# WS2812_MATRIX_2.net
KiCad netlist of a schematic drawn in Altium Designer
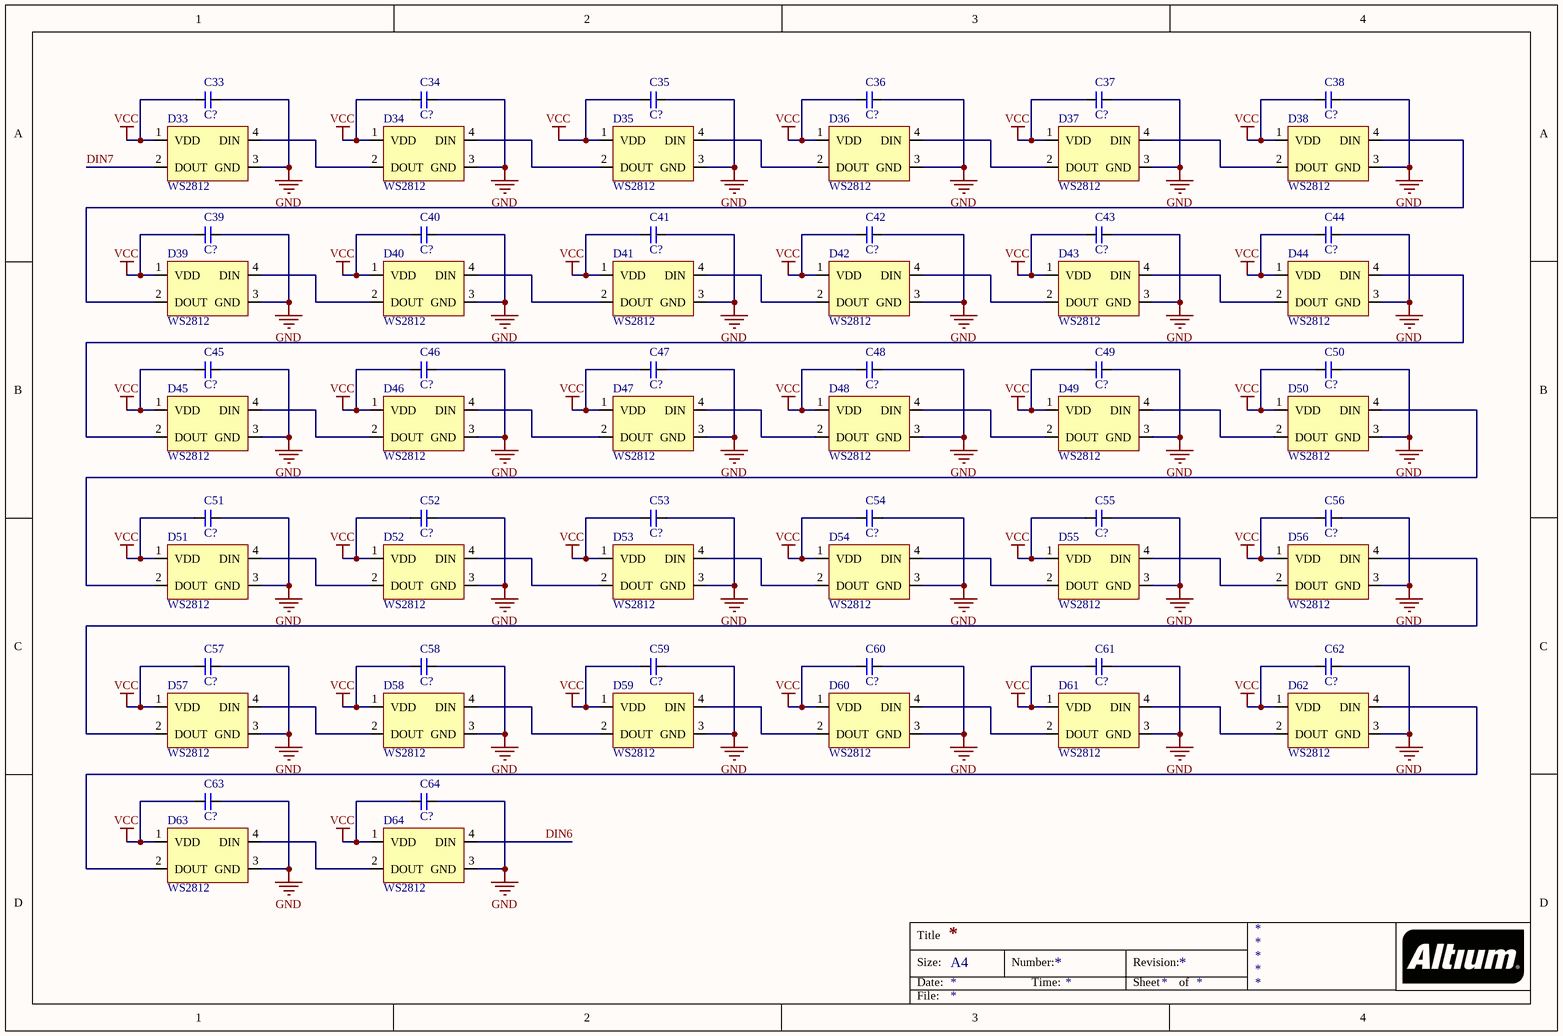
[diagram p0: WS2812_MATRIX_2.SchDoc]

(export (version "E")
  (design (tool "Eeschema 10.0.6"))
  (components
    (comp (ref "C33")
      (value "C?")
      (footprint "C0603")
      (description "Cap")
      (libsource (lib "SCH_Bacsic") (part "CAP"))
    )
    (comp (ref "C34")
      (value "C?")
      (footprint "C0603")
      (description "Cap")
      (libsource (lib "SCH_Bacsic") (part "CAP"))
    )
    (comp (ref "C35")
      (value "C?")
      (footprint "C0603")
      (description "Cap")
      (libsource (lib "SCH_Bacsic") (part "CAP"))
    )
    (comp (ref "C36")
      (value "C?")
      (footprint "C0603")
      (description "Cap")
      (libsource (lib "SCH_Bacsic") (part "CAP"))
    )
    (comp (ref "C37")
      (value "C?")
      (footprint "C0603")
      (description "Cap")
      (libsource (lib "SCH_Bacsic") (part "CAP"))
    )
    (comp (ref "C38")
      (value "C?")
      (footprint "C0603")
      (description "Cap")
      (libsource (lib "SCH_Bacsic") (part "CAP"))
    )
    (comp (ref "C39")
      (value "C?")
      (footprint "C0603")
      (description "Cap")
      (libsource (lib "SCH_Bacsic") (part "CAP"))
    )
    (comp (ref "C40")
      (value "C?")
      (footprint "C0603")
      (description "Cap")
      (libsource (lib "SCH_Bacsic") (part "CAP"))
    )
    (comp (ref "C41")
      (value "C?")
      (footprint "C0603")
      (description "Cap")
      (libsource (lib "SCH_Bacsic") (part "CAP"))
    )
    (comp (ref "C42")
      (value "C?")
      (footprint "C0603")
      (description "Cap")
      (libsource (lib "SCH_Bacsic") (part "CAP"))
    )
    (comp (ref "C43")
      (value "C?")
      (footprint "C0603")
      (description "Cap")
      (libsource (lib "SCH_Bacsic") (part "CAP"))
    )
    (comp (ref "C44")
      (value "C?")
      (footprint "C0603")
      (description "Cap")
      (libsource (lib "SCH_Bacsic") (part "CAP"))
    )
    (comp (ref "C45")
      (value "C?")
      (footprint "C0603")
      (description "Cap")
      (libsource (lib "SCH_Bacsic") (part "CAP"))
    )
    (comp (ref "C46")
      (value "C?")
      (footprint "C0603")
      (description "Cap")
      (libsource (lib "SCH_Bacsic") (part "CAP"))
    )
    (comp (ref "C47")
      (value "C?")
      (footprint "C0603")
      (description "Cap")
      (libsource (lib "SCH_Bacsic") (part "CAP"))
    )
    (comp (ref "C48")
      (value "C?")
      (footprint "C0603")
      (description "Cap")
      (libsource (lib "SCH_Bacsic") (part "CAP"))
    )
    (comp (ref "C49")
      (value "C?")
      (footprint "C0603")
      (description "Cap")
      (libsource (lib "SCH_Bacsic") (part "CAP"))
    )
    (comp (ref "C50")
      (value "C?")
      (footprint "C0603")
      (description "Cap")
      (libsource (lib "SCH_Bacsic") (part "CAP"))
    )
    (comp (ref "C51")
      (value "C?")
      (footprint "C0603")
      (description "Cap")
      (libsource (lib "SCH_Bacsic") (part "CAP"))
    )
    (comp (ref "C52")
      (value "C?")
      (footprint "C0603")
      (description "Cap")
      (libsource (lib "SCH_Bacsic") (part "CAP"))
    )
    (comp (ref "C53")
      (value "C?")
      (footprint "C0603")
      (description "Cap")
      (libsource (lib "SCH_Bacsic") (part "CAP"))
    )
    (comp (ref "C54")
      (value "C?")
      (footprint "C0603")
      (description "Cap")
      (libsource (lib "SCH_Bacsic") (part "CAP"))
    )
    (comp (ref "C55")
      (value "C?")
      (footprint "C0603")
      (description "Cap")
      (libsource (lib "SCH_Bacsic") (part "CAP"))
    )
    (comp (ref "C56")
      (value "C?")
      (footprint "C0603")
      (description "Cap")
      (libsource (lib "SCH_Bacsic") (part "CAP"))
    )
    (comp (ref "C57")
      (value "C?")
      (footprint "C0603")
      (description "Cap")
      (libsource (lib "SCH_Bacsic") (part "CAP"))
    )
    (comp (ref "C58")
      (value "C?")
      (footprint "C0603")
      (description "Cap")
      (libsource (lib "SCH_Bacsic") (part "CAP"))
    )
    (comp (ref "C59")
      (value "C?")
      (footprint "C0603")
      (description "Cap")
      (libsource (lib "SCH_Bacsic") (part "CAP"))
    )
    (comp (ref "C60")
      (value "C?")
      (footprint "C0603")
      (description "Cap")
      (libsource (lib "SCH_Bacsic") (part "CAP"))
    )
    (comp (ref "C61")
      (value "C?")
      (footprint "C0603")
      (description "Cap")
      (libsource (lib "SCH_Bacsic") (part "CAP"))
    )
    (comp (ref "C62")
      (value "C?")
      (footprint "C0603")
      (description "Cap")
      (libsource (lib "SCH_Bacsic") (part "CAP"))
    )
    (comp (ref "C63")
      (value "C?")
      (footprint "C0603")
      (description "Cap")
      (libsource (lib "SCH_Bacsic") (part "CAP"))
    )
    (comp (ref "C64")
      (value "C?")
      (footprint "C0603")
      (description "Cap")
      (libsource (lib "SCH_Bacsic") (part "CAP"))
    )
    (comp (ref "D33")
      (value "WS2812")
      (footprint "WS2812_3528")
      (libsource (lib "SCH_Bacsic") (part "WS2812"))
    )
    (comp (ref "D34")
      (value "WS2812")
      (footprint "WS2812_3528")
      (libsource (lib "SCH_Bacsic") (part "WS2812"))
    )
    (comp (ref "D35")
      (value "WS2812")
      (footprint "WS2812_3528")
      (libsource (lib "SCH_Bacsic") (part "WS2812"))
    )
    (comp (ref "D36")
      (value "WS2812")
      (footprint "WS2812_3528")
      (libsource (lib "SCH_Bacsic") (part "WS2812"))
    )
    (comp (ref "D37")
      (value "WS2812")
      (footprint "WS2812_3528")
      (libsource (lib "SCH_Bacsic") (part "WS2812"))
    )
    (comp (ref "D38")
      (value "WS2812")
      (footprint "WS2812_3528")
      (libsource (lib "SCH_Bacsic") (part "WS2812"))
    )
    (comp (ref "D39")
      (value "WS2812")
      (footprint "WS2812_3528")
      (libsource (lib "SCH_Bacsic") (part "WS2812"))
    )
    (comp (ref "D40")
      (value "WS2812")
      (footprint "WS2812_3528")
      (libsource (lib "SCH_Bacsic") (part "WS2812"))
    )
    (comp (ref "D41")
      (value "WS2812")
      (footprint "WS2812_3528")
      (libsource (lib "SCH_Bacsic") (part "WS2812"))
    )
    (comp (ref "D42")
      (value "WS2812")
      (footprint "WS2812_3528")
      (libsource (lib "SCH_Bacsic") (part "WS2812"))
    )
    (comp (ref "D43")
      (value "WS2812")
      (footprint "WS2812_3528")
      (libsource (lib "SCH_Bacsic") (part "WS2812"))
    )
    (comp (ref "D44")
      (value "WS2812")
      (footprint "WS2812_3528")
      (libsource (lib "SCH_Bacsic") (part "WS2812"))
    )
    (comp (ref "D45")
      (value "WS2812")
      (footprint "WS2812_3528")
      (libsource (lib "SCH_Bacsic") (part "WS2812"))
    )
    (comp (ref "D46")
      (value "WS2812")
      (footprint "WS2812_3528")
      (libsource (lib "SCH_Bacsic") (part "WS2812"))
    )
    (comp (ref "D47")
      (value "WS2812")
      (footprint "WS2812_3528")
      (libsource (lib "SCH_Bacsic") (part "WS2812"))
    )
    (comp (ref "D48")
      (value "WS2812")
      (footprint "WS2812_3528")
      (libsource (lib "SCH_Bacsic") (part "WS2812"))
    )
    (comp (ref "D49")
      (value "WS2812")
      (footprint "WS2812_3528")
      (libsource (lib "SCH_Bacsic") (part "WS2812"))
    )
    (comp (ref "D50")
      (value "WS2812")
      (footprint "WS2812_3528")
      (libsource (lib "SCH_Bacsic") (part "WS2812"))
    )
    (comp (ref "D51")
      (value "WS2812")
      (footprint "WS2812_3528")
      (libsource (lib "SCH_Bacsic") (part "WS2812"))
    )
    (comp (ref "D52")
      (value "WS2812")
      (footprint "WS2812_3528")
      (libsource (lib "SCH_Bacsic") (part "WS2812"))
    )
    (comp (ref "D53")
      (value "WS2812")
      (footprint "WS2812_3528")
      (libsource (lib "SCH_Bacsic") (part "WS2812"))
    )
    (comp (ref "D54")
      (value "WS2812")
      (footprint "WS2812_3528")
      (libsource (lib "SCH_Bacsic") (part "WS2812"))
    )
    (comp (ref "D55")
      (value "WS2812")
      (footprint "WS2812_3528")
      (libsource (lib "SCH_Bacsic") (part "WS2812"))
    )
    (comp (ref "D56")
      (value "WS2812")
      (footprint "WS2812_3528")
      (libsource (lib "SCH_Bacsic") (part "WS2812"))
    )
    (comp (ref "D57")
      (value "WS2812")
      (footprint "WS2812_3528")
      (libsource (lib "SCH_Bacsic") (part "WS2812"))
    )
    (comp (ref "D58")
      (value "WS2812")
      (footprint "WS2812_3528")
      (libsource (lib "SCH_Bacsic") (part "WS2812"))
    )
    (comp (ref "D59")
      (value "WS2812")
      (footprint "WS2812_3528")
      (libsource (lib "SCH_Bacsic") (part "WS2812"))
    )
    (comp (ref "D60")
      (value "WS2812")
      (footprint "WS2812_3528")
      (libsource (lib "SCH_Bacsic") (part "WS2812"))
    )
    (comp (ref "D61")
      (value "WS2812")
      (footprint "WS2812_3528")
      (libsource (lib "SCH_Bacsic") (part "WS2812"))
    )
    (comp (ref "D62")
      (value "WS2812")
      (footprint "WS2812_3528")
      (libsource (lib "SCH_Bacsic") (part "WS2812"))
    )
    (comp (ref "D63")
      (value "WS2812")
      (footprint "WS2812_3528")
      (libsource (lib "SCH_Bacsic") (part "WS2812"))
    )
    (comp (ref "D64")
      (value "WS2812")
      (footprint "WS2812_3528")
      (libsource (lib "SCH_Bacsic") (part "WS2812"))
    )
  )
  (nets
    (net (code "1") (name "/DIN6") (class "Default")
      (node (ref "D64") (pin "4") (pinfunction "DIN_4") (pintype "passive"))
    )
    (net (code "2") (name "/DIN7") (class "Default")
      (node (ref "D33") (pin "2") (pinfunction "DOUT_2") (pintype "passive"))
    )
    (net (code "3") (name "GND") (class "Default")
      (node (ref "C33") (pin "2") (pintype "passive"))
      (node (ref "C34") (pin "2") (pintype "passive"))
      (node (ref "C35") (pin "2") (pintype "passive"))
      (node (ref "C36") (pin "2") (pintype "passive"))
      (node (ref "C37") (pin "2") (pintype "passive"))
      (node (ref "C38") (pin "2") (pintype "passive"))
      (node (ref "C39") (pin "2") (pintype "passive"))
      (node (ref "C40") (pin "2") (pintype "passive"))
      (node (ref "C41") (pin "2") (pintype "passive"))
      (node (ref "C42") (pin "2") (pintype "passive"))
      (node (ref "C43") (pin "2") (pintype "passive"))
      (node (ref "C44") (pin "2") (pintype "passive"))
      (node (ref "C45") (pin "2") (pintype "passive"))
      (node (ref "C46") (pin "2") (pintype "passive"))
      (node (ref "C47") (pin "2") (pintype "passive"))
      (node (ref "C48") (pin "2") (pintype "passive"))
      (node (ref "C49") (pin "2") (pintype "passive"))
      (node (ref "C50") (pin "2") (pintype "passive"))
      (node (ref "C51") (pin "2") (pintype "passive"))
      (node (ref "C52") (pin "2") (pintype "passive"))
      (node (ref "C53") (pin "2") (pintype "passive"))
      (node (ref "C54") (pin "2") (pintype "passive"))
      (node (ref "C55") (pin "2") (pintype "passive"))
      (node (ref "C56") (pin "2") (pintype "passive"))
      (node (ref "C57") (pin "2") (pintype "passive"))
      (node (ref "C58") (pin "2") (pintype "passive"))
      (node (ref "C59") (pin "2") (pintype "passive"))
      (node (ref "C60") (pin "2") (pintype "passive"))
      (node (ref "C61") (pin "2") (pintype "passive"))
      (node (ref "C62") (pin "2") (pintype "passive"))
      (node (ref "C63") (pin "2") (pintype "passive"))
      (node (ref "C64") (pin "2") (pintype "passive"))
      (node (ref "D33") (pin "3") (pinfunction "GND_3") (pintype "passive"))
      (node (ref "D34") (pin "3") (pinfunction "GND_3") (pintype "passive"))
      (node (ref "D35") (pin "3") (pinfunction "GND_3") (pintype "passive"))
      (node (ref "D36") (pin "3") (pinfunction "GND_3") (pintype "passive"))
      (node (ref "D37") (pin "3") (pinfunction "GND_3") (pintype "passive"))
      (node (ref "D38") (pin "3") (pinfunction "GND_3") (pintype "passive"))
      (node (ref "D39") (pin "3") (pinfunction "GND_3") (pintype "passive"))
      (node (ref "D40") (pin "3") (pinfunction "GND_3") (pintype "passive"))
      (node (ref "D41") (pin "3") (pinfunction "GND_3") (pintype "passive"))
      (node (ref "D42") (pin "3") (pinfunction "GND_3") (pintype "passive"))
      (node (ref "D43") (pin "3") (pinfunction "GND_3") (pintype "passive"))
      (node (ref "D44") (pin "3") (pinfunction "GND_3") (pintype "passive"))
      (node (ref "D45") (pin "3") (pinfunction "GND_3") (pintype "passive"))
      (node (ref "D46") (pin "3") (pinfunction "GND_3") (pintype "passive"))
      (node (ref "D47") (pin "3") (pinfunction "GND_3") (pintype "passive"))
      (node (ref "D48") (pin "3") (pinfunction "GND_3") (pintype "passive"))
      (node (ref "D49") (pin "3") (pinfunction "GND_3") (pintype "passive"))
      (node (ref "D50") (pin "3") (pinfunction "GND_3") (pintype "passive"))
      (node (ref "D51") (pin "3") (pinfunction "GND_3") (pintype "passive"))
      (node (ref "D52") (pin "3") (pinfunction "GND_3") (pintype "passive"))
      (node (ref "D53") (pin "3") (pinfunction "GND_3") (pintype "passive"))
      (node (ref "D54") (pin "3") (pinfunction "GND_3") (pintype "passive"))
      (node (ref "D55") (pin "3") (pinfunction "GND_3") (pintype "passive"))
      (node (ref "D56") (pin "3") (pinfunction "GND_3") (pintype "passive"))
      (node (ref "D57") (pin "3") (pinfunction "GND_3") (pintype "passive"))
      (node (ref "D58") (pin "3") (pinfunction "GND_3") (pintype "passive"))
      (node (ref "D59") (pin "3") (pinfunction "GND_3") (pintype "passive"))
      (node (ref "D60") (pin "3") (pinfunction "GND_3") (pintype "passive"))
      (node (ref "D61") (pin "3") (pinfunction "GND_3") (pintype "passive"))
      (node (ref "D62") (pin "3") (pinfunction "GND_3") (pintype "passive"))
      (node (ref "D63") (pin "3") (pinfunction "GND_3") (pintype "passive"))
      (node (ref "D64") (pin "3") (pinfunction "GND_3") (pintype "passive"))
    )
    (net (code "4") (name "Net-(D33-DIN)") (class "Default")
      (node (ref "D33") (pin "4") (pinfunction "DIN_4") (pintype "passive"))
      (node (ref "D34") (pin "2") (pinfunction "DOUT_2") (pintype "passive"))
    )
    (net (code "5") (name "Net-(D34-DIN)") (class "Default")
      (node (ref "D34") (pin "4") (pinfunction "DIN_4") (pintype "passive"))
      (node (ref "D35") (pin "2") (pinfunction "DOUT_2") (pintype "passive"))
    )
    (net (code "6") (name "Net-(D35-DIN)") (class "Default")
      (node (ref "D35") (pin "4") (pinfunction "DIN_4") (pintype "passive"))
      (node (ref "D36") (pin "2") (pinfunction "DOUT_2") (pintype "passive"))
    )
    (net (code "7") (name "Net-(D36-DIN)") (class "Default")
      (node (ref "D36") (pin "4") (pinfunction "DIN_4") (pintype "passive"))
      (node (ref "D37") (pin "2") (pinfunction "DOUT_2") (pintype "passive"))
    )
    (net (code "8") (name "Net-(D37-DIN)") (class "Default")
      (node (ref "D37") (pin "4") (pinfunction "DIN_4") (pintype "passive"))
      (node (ref "D38") (pin "2") (pinfunction "DOUT_2") (pintype "passive"))
    )
    (net (code "9") (name "Net-(D38-DIN)") (class "Default")
      (node (ref "D38") (pin "4") (pinfunction "DIN_4") (pintype "passive"))
      (node (ref "D39") (pin "2") (pinfunction "DOUT_2") (pintype "passive"))
    )
    (net (code "10") (name "Net-(D39-DIN)") (class "Default")
      (node (ref "D39") (pin "4") (pinfunction "DIN_4") (pintype "passive"))
      (node (ref "D40") (pin "2") (pinfunction "DOUT_2") (pintype "passive"))
    )
    (net (code "11") (name "Net-(D40-DIN)") (class "Default")
      (node (ref "D40") (pin "4") (pinfunction "DIN_4") (pintype "passive"))
      (node (ref "D41") (pin "2") (pinfunction "DOUT_2") (pintype "passive"))
    )
    (net (code "12") (name "Net-(D41-DIN)") (class "Default")
      (node (ref "D41") (pin "4") (pinfunction "DIN_4") (pintype "passive"))
      (node (ref "D42") (pin "2") (pinfunction "DOUT_2") (pintype "passive"))
    )
    (net (code "13") (name "Net-(D42-DIN)") (class "Default")
      (node (ref "D42") (pin "4") (pinfunction "DIN_4") (pintype "passive"))
      (node (ref "D43") (pin "2") (pinfunction "DOUT_2") (pintype "passive"))
    )
    (net (code "14") (name "Net-(D43-DIN)") (class "Default")
      (node (ref "D43") (pin "4") (pinfunction "DIN_4") (pintype "passive"))
      (node (ref "D44") (pin "2") (pinfunction "DOUT_2") (pintype "passive"))
    )
    (net (code "15") (name "Net-(D44-DIN)") (class "Default")
      (node (ref "D44") (pin "4") (pinfunction "DIN_4") (pintype "passive"))
      (node (ref "D45") (pin "2") (pinfunction "DOUT_2") (pintype "passive"))
    )
    (net (code "16") (name "Net-(D45-DIN)") (class "Default")
      (node (ref "D45") (pin "4") (pinfunction "DIN_4") (pintype "passive"))
      (node (ref "D46") (pin "2") (pinfunction "DOUT_2") (pintype "passive"))
    )
    (net (code "17") (name "Net-(D46-DIN)") (class "Default")
      (node (ref "D46") (pin "4") (pinfunction "DIN_4") (pintype "passive"))
      (node (ref "D47") (pin "2") (pinfunction "DOUT_2") (pintype "passive"))
    )
    (net (code "18") (name "Net-(D47-DIN)") (class "Default")
      (node (ref "D47") (pin "4") (pinfunction "DIN_4") (pintype "passive"))
      (node (ref "D48") (pin "2") (pinfunction "DOUT_2") (pintype "passive"))
    )
    (net (code "19") (name "Net-(D48-DIN)") (class "Default")
      (node (ref "D48") (pin "4") (pinfunction "DIN_4") (pintype "passive"))
      (node (ref "D49") (pin "2") (pinfunction "DOUT_2") (pintype "passive"))
    )
    (net (code "20") (name "Net-(D49-DIN)") (class "Default")
      (node (ref "D49") (pin "4") (pinfunction "DIN_4") (pintype "passive"))
      (node (ref "D50") (pin "2") (pinfunction "DOUT_2") (pintype "passive"))
    )
    (net (code "21") (name "Net-(D50-DIN)") (class "Default")
      (node (ref "D50") (pin "4") (pinfunction "DIN_4") (pintype "passive"))
      (node (ref "D51") (pin "2") (pinfunction "DOUT_2") (pintype "passive"))
    )
    (net (code "22") (name "Net-(D51-DIN)") (class "Default")
      (node (ref "D51") (pin "4") (pinfunction "DIN_4") (pintype "passive"))
      (node (ref "D52") (pin "2") (pinfunction "DOUT_2") (pintype "passive"))
    )
    (net (code "23") (name "Net-(D52-DIN)") (class "Default")
      (node (ref "D52") (pin "4") (pinfunction "DIN_4") (pintype "passive"))
      (node (ref "D53") (pin "2") (pinfunction "DOUT_2") (pintype "passive"))
    )
    (net (code "24") (name "Net-(D53-DIN)") (class "Default")
      (node (ref "D53") (pin "4") (pinfunction "DIN_4") (pintype "passive"))
      (node (ref "D54") (pin "2") (pinfunction "DOUT_2") (pintype "passive"))
    )
    (net (code "25") (name "Net-(D54-DIN)") (class "Default")
      (node (ref "D54") (pin "4") (pinfunction "DIN_4") (pintype "passive"))
      (node (ref "D55") (pin "2") (pinfunction "DOUT_2") (pintype "passive"))
    )
    (net (code "26") (name "Net-(D55-DIN)") (class "Default")
      (node (ref "D55") (pin "4") (pinfunction "DIN_4") (pintype "passive"))
      (node (ref "D56") (pin "2") (pinfunction "DOUT_2") (pintype "passive"))
    )
    (net (code "27") (name "Net-(D56-DIN)") (class "Default")
      (node (ref "D56") (pin "4") (pinfunction "DIN_4") (pintype "passive"))
      (node (ref "D57") (pin "2") (pinfunction "DOUT_2") (pintype "passive"))
    )
    (net (code "28") (name "Net-(D57-DIN)") (class "Default")
      (node (ref "D57") (pin "4") (pinfunction "DIN_4") (pintype "passive"))
      (node (ref "D58") (pin "2") (pinfunction "DOUT_2") (pintype "passive"))
    )
    (net (code "29") (name "Net-(D58-DIN)") (class "Default")
      (node (ref "D58") (pin "4") (pinfunction "DIN_4") (pintype "passive"))
      (node (ref "D59") (pin "2") (pinfunction "DOUT_2") (pintype "passive"))
    )
    (net (code "30") (name "Net-(D59-DIN)") (class "Default")
      (node (ref "D59") (pin "4") (pinfunction "DIN_4") (pintype "passive"))
      (node (ref "D60") (pin "2") (pinfunction "DOUT_2") (pintype "passive"))
    )
    (net (code "31") (name "Net-(D60-DIN)") (class "Default")
      (node (ref "D60") (pin "4") (pinfunction "DIN_4") (pintype "passive"))
      (node (ref "D61") (pin "2") (pinfunction "DOUT_2") (pintype "passive"))
    )
    (net (code "32") (name "Net-(D61-DIN)") (class "Default")
      (node (ref "D61") (pin "4") (pinfunction "DIN_4") (pintype "passive"))
      (node (ref "D62") (pin "2") (pinfunction "DOUT_2") (pintype "passive"))
    )
    (net (code "33") (name "Net-(D62-DIN)") (class "Default")
      (node (ref "D62") (pin "4") (pinfunction "DIN_4") (pintype "passive"))
      (node (ref "D63") (pin "2") (pinfunction "DOUT_2") (pintype "passive"))
    )
    (net (code "34") (name "Net-(D63-DIN)") (class "Default")
      (node (ref "D63") (pin "4") (pinfunction "DIN_4") (pintype "passive"))
      (node (ref "D64") (pin "2") (pinfunction "DOUT_2") (pintype "passive"))
    )
    (net (code "35") (name "VCC") (class "Default")
      (node (ref "C33") (pin "1") (pintype "passive"))
      (node (ref "C34") (pin "1") (pintype "passive"))
      (node (ref "C35") (pin "1") (pintype "passive"))
      (node (ref "C36") (pin "1") (pintype "passive"))
      (node (ref "C37") (pin "1") (pintype "passive"))
      (node (ref "C38") (pin "1") (pintype "passive"))
      (node (ref "C39") (pin "1") (pintype "passive"))
      (node (ref "C40") (pin "1") (pintype "passive"))
      (node (ref "C41") (pin "1") (pintype "passive"))
      (node (ref "C42") (pin "1") (pintype "passive"))
      (node (ref "C43") (pin "1") (pintype "passive"))
      (node (ref "C44") (pin "1") (pintype "passive"))
      (node (ref "C45") (pin "1") (pintype "passive"))
      (node (ref "C46") (pin "1") (pintype "passive"))
      (node (ref "C47") (pin "1") (pintype "passive"))
      (node (ref "C48") (pin "1") (pintype "passive"))
      (node (ref "C49") (pin "1") (pintype "passive"))
      (node (ref "C50") (pin "1") (pintype "passive"))
      (node (ref "C51") (pin "1") (pintype "passive"))
      (node (ref "C52") (pin "1") (pintype "passive"))
      (node (ref "C53") (pin "1") (pintype "passive"))
      (node (ref "C54") (pin "1") (pintype "passive"))
      (node (ref "C55") (pin "1") (pintype "passive"))
      (node (ref "C56") (pin "1") (pintype "passive"))
      (node (ref "C57") (pin "1") (pintype "passive"))
      (node (ref "C58") (pin "1") (pintype "passive"))
      (node (ref "C59") (pin "1") (pintype "passive"))
      (node (ref "C60") (pin "1") (pintype "passive"))
      (node (ref "C61") (pin "1") (pintype "passive"))
      (node (ref "C62") (pin "1") (pintype "passive"))
      (node (ref "C63") (pin "1") (pintype "passive"))
      (node (ref "C64") (pin "1") (pintype "passive"))
      (node (ref "D33") (pin "1") (pinfunction "VDD_1") (pintype "passive"))
      (node (ref "D34") (pin "1") (pinfunction "VDD_1") (pintype "passive"))
      (node (ref "D35") (pin "1") (pinfunction "VDD_1") (pintype "passive"))
      (node (ref "D36") (pin "1") (pinfunction "VDD_1") (pintype "passive"))
      (node (ref "D37") (pin "1") (pinfunction "VDD_1") (pintype "passive"))
      (node (ref "D38") (pin "1") (pinfunction "VDD_1") (pintype "passive"))
      (node (ref "D39") (pin "1") (pinfunction "VDD_1") (pintype "passive"))
      (node (ref "D40") (pin "1") (pinfunction "VDD_1") (pintype "passive"))
      (node (ref "D41") (pin "1") (pinfunction "VDD_1") (pintype "passive"))
      (node (ref "D42") (pin "1") (pinfunction "VDD_1") (pintype "passive"))
      (node (ref "D43") (pin "1") (pinfunction "VDD_1") (pintype "passive"))
      (node (ref "D44") (pin "1") (pinfunction "VDD_1") (pintype "passive"))
      (node (ref "D45") (pin "1") (pinfunction "VDD_1") (pintype "passive"))
      (node (ref "D46") (pin "1") (pinfunction "VDD_1") (pintype "passive"))
      (node (ref "D47") (pin "1") (pinfunction "VDD_1") (pintype "passive"))
      (node (ref "D48") (pin "1") (pinfunction "VDD_1") (pintype "passive"))
      (node (ref "D49") (pin "1") (pinfunction "VDD_1") (pintype "passive"))
      (node (ref "D50") (pin "1") (pinfunction "VDD_1") (pintype "passive"))
      (node (ref "D51") (pin "1") (pinfunction "VDD_1") (pintype "passive"))
      (node (ref "D52") (pin "1") (pinfunction "VDD_1") (pintype "passive"))
      (node (ref "D53") (pin "1") (pinfunction "VDD_1") (pintype "passive"))
      (node (ref "D54") (pin "1") (pinfunction "VDD_1") (pintype "passive"))
      (node (ref "D55") (pin "1") (pinfunction "VDD_1") (pintype "passive"))
      (node (ref "D56") (pin "1") (pinfunction "VDD_1") (pintype "passive"))
      (node (ref "D57") (pin "1") (pinfunction "VDD_1") (pintype "passive"))
      (node (ref "D58") (pin "1") (pinfunction "VDD_1") (pintype "passive"))
      (node (ref "D59") (pin "1") (pinfunction "VDD_1") (pintype "passive"))
      (node (ref "D60") (pin "1") (pinfunction "VDD_1") (pintype "passive"))
      (node (ref "D61") (pin "1") (pinfunction "VDD_1") (pintype "passive"))
      (node (ref "D62") (pin "1") (pinfunction "VDD_1") (pintype "passive"))
      (node (ref "D63") (pin "1") (pinfunction "VDD_1") (pintype "passive"))
      (node (ref "D64") (pin "1") (pinfunction "VDD_1") (pintype "passive"))
    )
  )
)
